# door.net
KiCad netlist of a schematic drawn in EAGLE
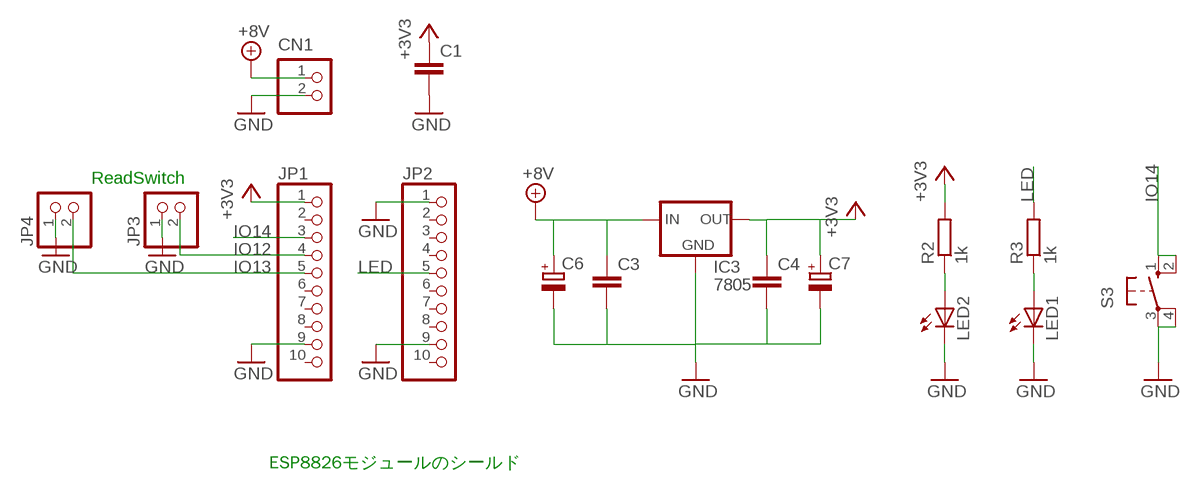
[diagram p0: schematic, sheet 1]

(export (version "E")
  (design (tool "Eeschema 10.0.6"))
  (components
    (comp (ref "C1")
      (value "C-EU050-024X044")
      (footprint "eagle-import:C050-024X044")
      (libsource (lib "eagle-import") (part "C-EU050-024X044"))
    )
    (comp (ref "C3")
      (value "C-EU050-024X044")
      (footprint "eagle-import:C050-024X044")
      (libsource (lib "eagle-import") (part "C-EU050-024X044"))
    )
    (comp (ref "C4")
      (value "C-EU050-024X044")
      (footprint "eagle-import:C050-024X044")
      (libsource (lib "eagle-import") (part "C-EU050-024X044"))
    )
    (comp (ref "C6")
      (value "CPOL-EUE5-4")
      (footprint "eagle-import:E5-4")
      (libsource (lib "eagle-import") (part "CPOL-EUE5-4"))
    )
    (comp (ref "C7")
      (value "CPOL-EUE5-4")
      (footprint "eagle-import:E5-4")
      (libsource (lib "eagle-import") (part "CPOL-EUE5-4"))
    )
    (comp (ref "CN1")
      (value "S2B-PH-K-S")
      (footprint "eagle-import:S2B-PH-K-S")
      (libsource (lib "eagle-import") (part "S2B-PH-K-S"))
    )
    (comp (ref "IC3")
      (value "7805")
      (footprint "eagle-import:TO220_V")
      (libsource (lib "eagle-import") (part "7805"))
    )
    (comp (ref "JP1")
      (value "PINHD-1X10")
      (footprint "eagle-import:1X10")
      (libsource (lib "eagle-import") (part "PINHD-1X10"))
    )
    (comp (ref "JP2")
      (value "PINHD-1X10")
      (footprint "eagle-import:1X10")
      (libsource (lib "eagle-import") (part "PINHD-1X10"))
    )
    (comp (ref "JP3")
      (value "PINHD-1X2/90")
      (footprint "eagle-import:1X02_90")
      (libsource (lib "eagle-import") (part "PINHD-1X2/90"))
    )
    (comp (ref "JP4")
      (value "PINHD-1X2/90")
      (footprint "eagle-import:1X02_90")
      (libsource (lib "eagle-import") (part "PINHD-1X2/90"))
    )
    (comp (ref "LED1")
      (value "LEDSML0603")
      (footprint "eagle-import:SML0603")
      (libsource (lib "eagle-import") (part "LEDSML0603"))
    )
    (comp (ref "LED2")
      (value "LEDSML0603")
      (footprint "eagle-import:SML0603")
      (libsource (lib "eagle-import") (part "LEDSML0603"))
    )
    (comp (ref "R2")
      (value "1k")
      (footprint "eagle-import:0207_10")
      (libsource (lib "eagle-import") (part "R-EU_0207/10"))
    )
    (comp (ref "R3")
      (value "1k")
      (footprint "eagle-import:0207_10")
      (libsource (lib "eagle-import") (part "R-EU_0207/10"))
    )
    (comp (ref "S3")
      (value "10-XX")
      (footprint "eagle-import:B3F-10XX")
      (fields (field (name "MPN") "B3F-1000"))
      (libsource (lib "eagle-import") (part "10-XX"))
    )
  )
  (nets
    (net (code "1") (name "+3V3") (class "Default")
      (node (ref "C1") (pin "1") (pinfunction "1_1") (pintype "passive"))
      (node (ref "C4") (pin "1") (pinfunction "1_1") (pintype "passive"))
      (node (ref "C7") (pin "+") (pinfunction "+_+") (pintype "passive"))
      (node (ref "IC3") (pin "3") (pinfunction "OUT_3") (pintype "passive"))
      (node (ref "JP1") (pin "1") (pinfunction "1_1") (pintype "passive"))
      (node (ref "R2") (pin "2") (pinfunction "2_2") (pintype "passive"))
    )
    (net (code "2") (name "+8V") (class "Default")
      (node (ref "C3") (pin "1") (pinfunction "1_1") (pintype "passive"))
      (node (ref "C6") (pin "+") (pinfunction "+_+") (pintype "passive"))
      (node (ref "CN1") (pin "1") (pinfunction "1_1") (pintype "passive"))
      (node (ref "IC3") (pin "1") (pinfunction "IN_1") (pintype "input"))
    )
    (net (code "3") (name "/IO12") (class "Default")
      (node (ref "JP1") (pin "4") (pinfunction "4_4") (pintype "passive"))
      (node (ref "JP3") (pin "2") (pinfunction "2_2") (pintype "passive"))
    )
    (net (code "4") (name "/IO13") (class "Default")
      (node (ref "JP1") (pin "5") (pinfunction "5_5") (pintype "passive"))
      (node (ref "JP4") (pin "2") (pinfunction "2_2") (pintype "passive"))
    )
    (net (code "5") (name "/IO14") (class "Default")
      (node (ref "JP1") (pin "3") (pinfunction "3_3") (pintype "passive"))
      (node (ref "S3") (pin "1") (pinfunction "S_1") (pintype "passive"))
      (node (ref "S3") (pin "2") (pinfunction "S1_2") (pintype "passive"))
    )
    (net (code "6") (name "/LED") (class "Default")
      (node (ref "JP2") (pin "5") (pinfunction "5_5") (pintype "passive"))
      (node (ref "R3") (pin "2") (pinfunction "2_2") (pintype "passive"))
    )
    (net (code "7") (name "GND") (class "Default")
      (node (ref "C1") (pin "2") (pinfunction "2_2") (pintype "passive"))
      (node (ref "C3") (pin "2") (pinfunction "2_2") (pintype "passive"))
      (node (ref "C4") (pin "2") (pinfunction "2_2") (pintype "passive"))
      (node (ref "C6") (pin "-") (pinfunction "-_-") (pintype "passive"))
      (node (ref "C7") (pin "-") (pinfunction "-_-") (pintype "passive"))
      (node (ref "CN1") (pin "2") (pinfunction "2_2") (pintype "passive"))
      (node (ref "IC3") (pin "2") (pinfunction "GND_2") (pintype "input"))
      (node (ref "JP1") (pin "9") (pinfunction "9_9") (pintype "passive"))
      (node (ref "JP2") (pin "1") (pinfunction "1_1") (pintype "passive"))
      (node (ref "JP2") (pin "9") (pinfunction "9_9") (pintype "passive"))
      (node (ref "JP3") (pin "1") (pinfunction "1_1") (pintype "passive"))
      (node (ref "JP4") (pin "1") (pinfunction "1_1") (pintype "passive"))
      (node (ref "LED1") (pin "C") (pinfunction "C_C") (pintype "passive"))
      (node (ref "LED2") (pin "C") (pinfunction "C_C") (pintype "passive"))
      (node (ref "S3") (pin "3") (pinfunction "P_3") (pintype "passive"))
      (node (ref "S3") (pin "4") (pinfunction "P1_4") (pintype "passive"))
    )
    (net (code "8") (name "Net-(LED1-PadA)") (class "Default")
      (node (ref "LED1") (pin "A") (pinfunction "A_A") (pintype "passive"))
      (node (ref "R3") (pin "1") (pinfunction "1_1") (pintype "passive"))
    )
    (net (code "9") (name "Net-(LED2-PadA)") (class "Default")
      (node (ref "LED2") (pin "A") (pinfunction "A_A") (pintype "passive"))
      (node (ref "R2") (pin "1") (pinfunction "1_1") (pintype "passive"))
    )
    (net (code "10") (name "unconnected-(JP1-Pad2)") (class "Default")
      (node (ref "JP1") (pin "2") (pinfunction "2_2") (pintype "passive"))
    )
    (net (code "11") (name "unconnected-(JP1-Pad6)") (class "Default")
      (node (ref "JP1") (pin "6") (pinfunction "6_6") (pintype "passive"))
    )
    (net (code "12") (name "unconnected-(JP1-Pad7)") (class "Default")
      (node (ref "JP1") (pin "7") (pinfunction "7_7") (pintype "passive"))
    )
    (net (code "13") (name "unconnected-(JP1-Pad8)") (class "Default")
      (node (ref "JP1") (pin "8") (pinfunction "8_8") (pintype "passive"))
    )
    (net (code "14") (name "unconnected-(JP1-Pad10)") (class "Default")
      (node (ref "JP1") (pin "10") (pinfunction "10_10") (pintype "passive"))
    )
    (net (code "15") (name "unconnected-(JP2-Pad2)") (class "Default")
      (node (ref "JP2") (pin "2") (pinfunction "2_2") (pintype "passive"))
    )
    (net (code "16") (name "unconnected-(JP2-Pad3)") (class "Default")
      (node (ref "JP2") (pin "3") (pinfunction "3_3") (pintype "passive"))
    )
    (net (code "17") (name "unconnected-(JP2-Pad4)") (class "Default")
      (node (ref "JP2") (pin "4") (pinfunction "4_4") (pintype "passive"))
    )
    (net (code "18") (name "unconnected-(JP2-Pad6)") (class "Default")
      (node (ref "JP2") (pin "6") (pinfunction "6_6") (pintype "passive"))
    )
    (net (code "19") (name "unconnected-(JP2-Pad7)") (class "Default")
      (node (ref "JP2") (pin "7") (pinfunction "7_7") (pintype "passive"))
    )
    (net (code "20") (name "unconnected-(JP2-Pad8)") (class "Default")
      (node (ref "JP2") (pin "8") (pinfunction "8_8") (pintype "passive"))
    )
    (net (code "21") (name "unconnected-(JP2-Pad10)") (class "Default")
      (node (ref "JP2") (pin "10") (pinfunction "10_10") (pintype "passive"))
    )
  )
)
